# axiom_beta_plugin_module_TE0714_SATA_v0_.net
KiCad netlist of a schematic drawn in EAGLE
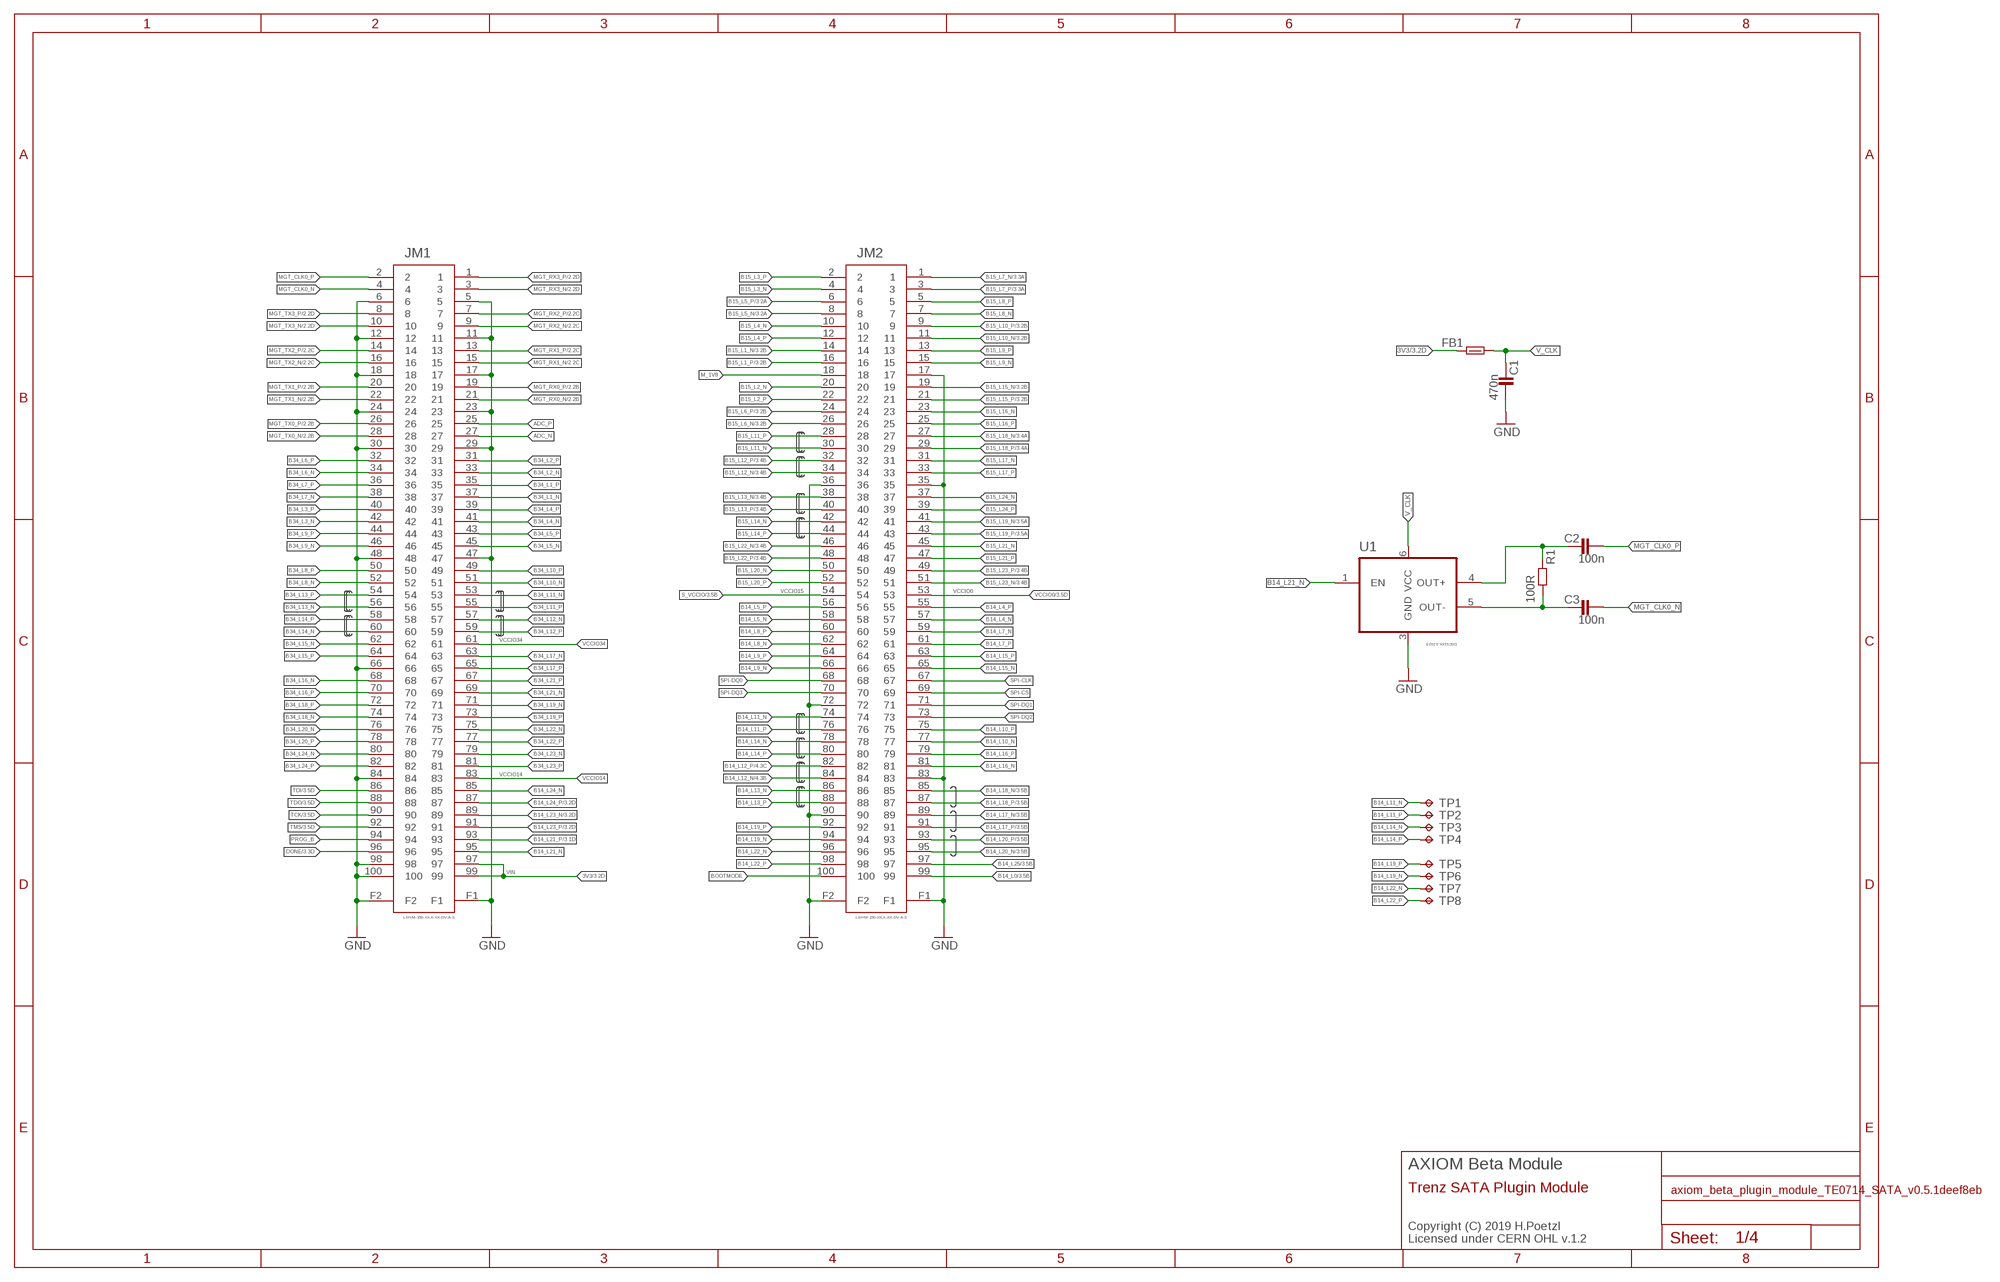
[diagram p0: schematic, sheet 1]
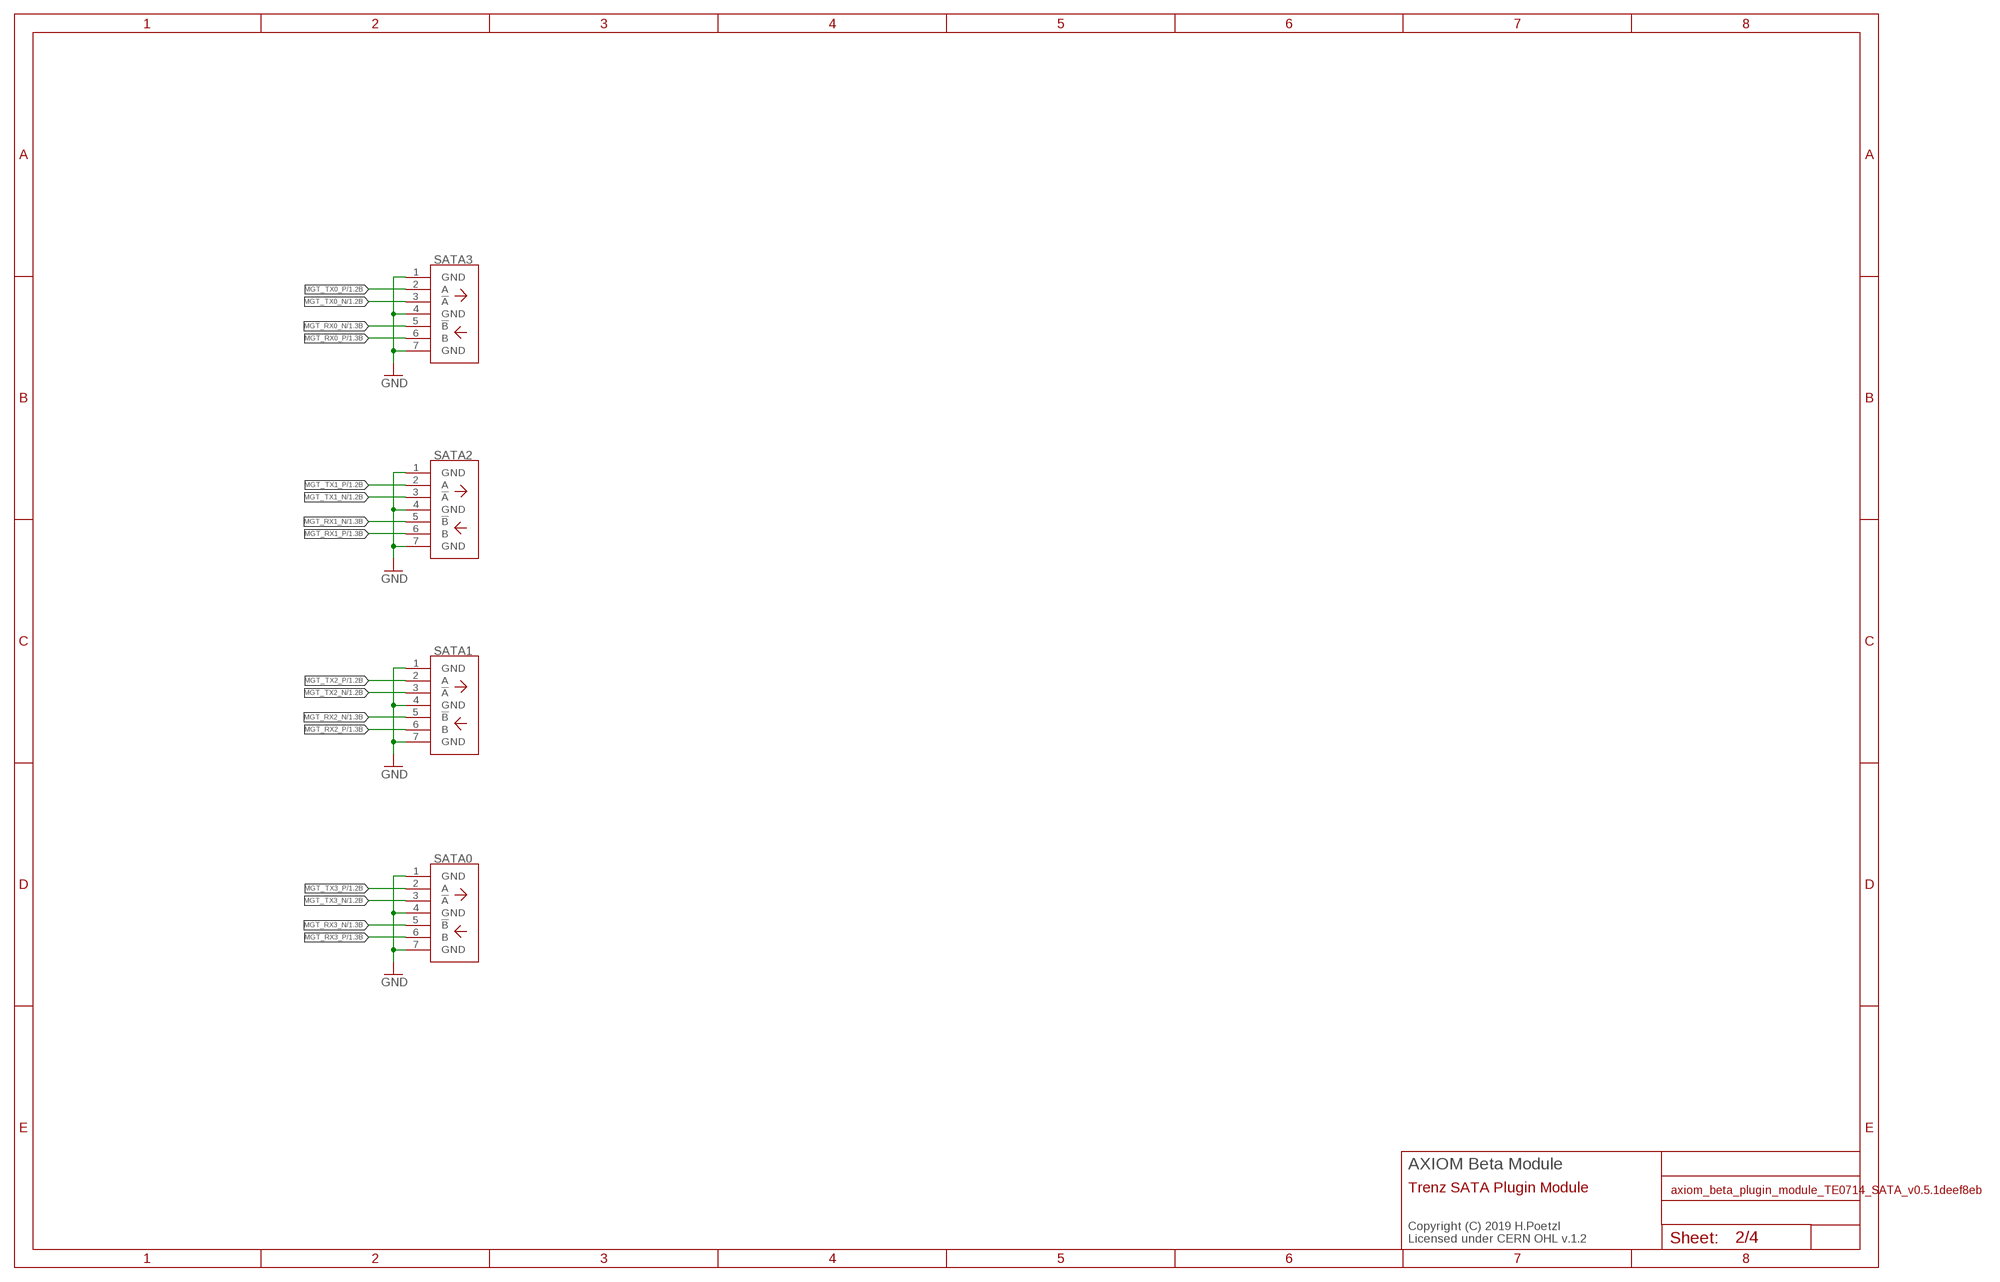
[diagram p1: schematic, sheet 2]
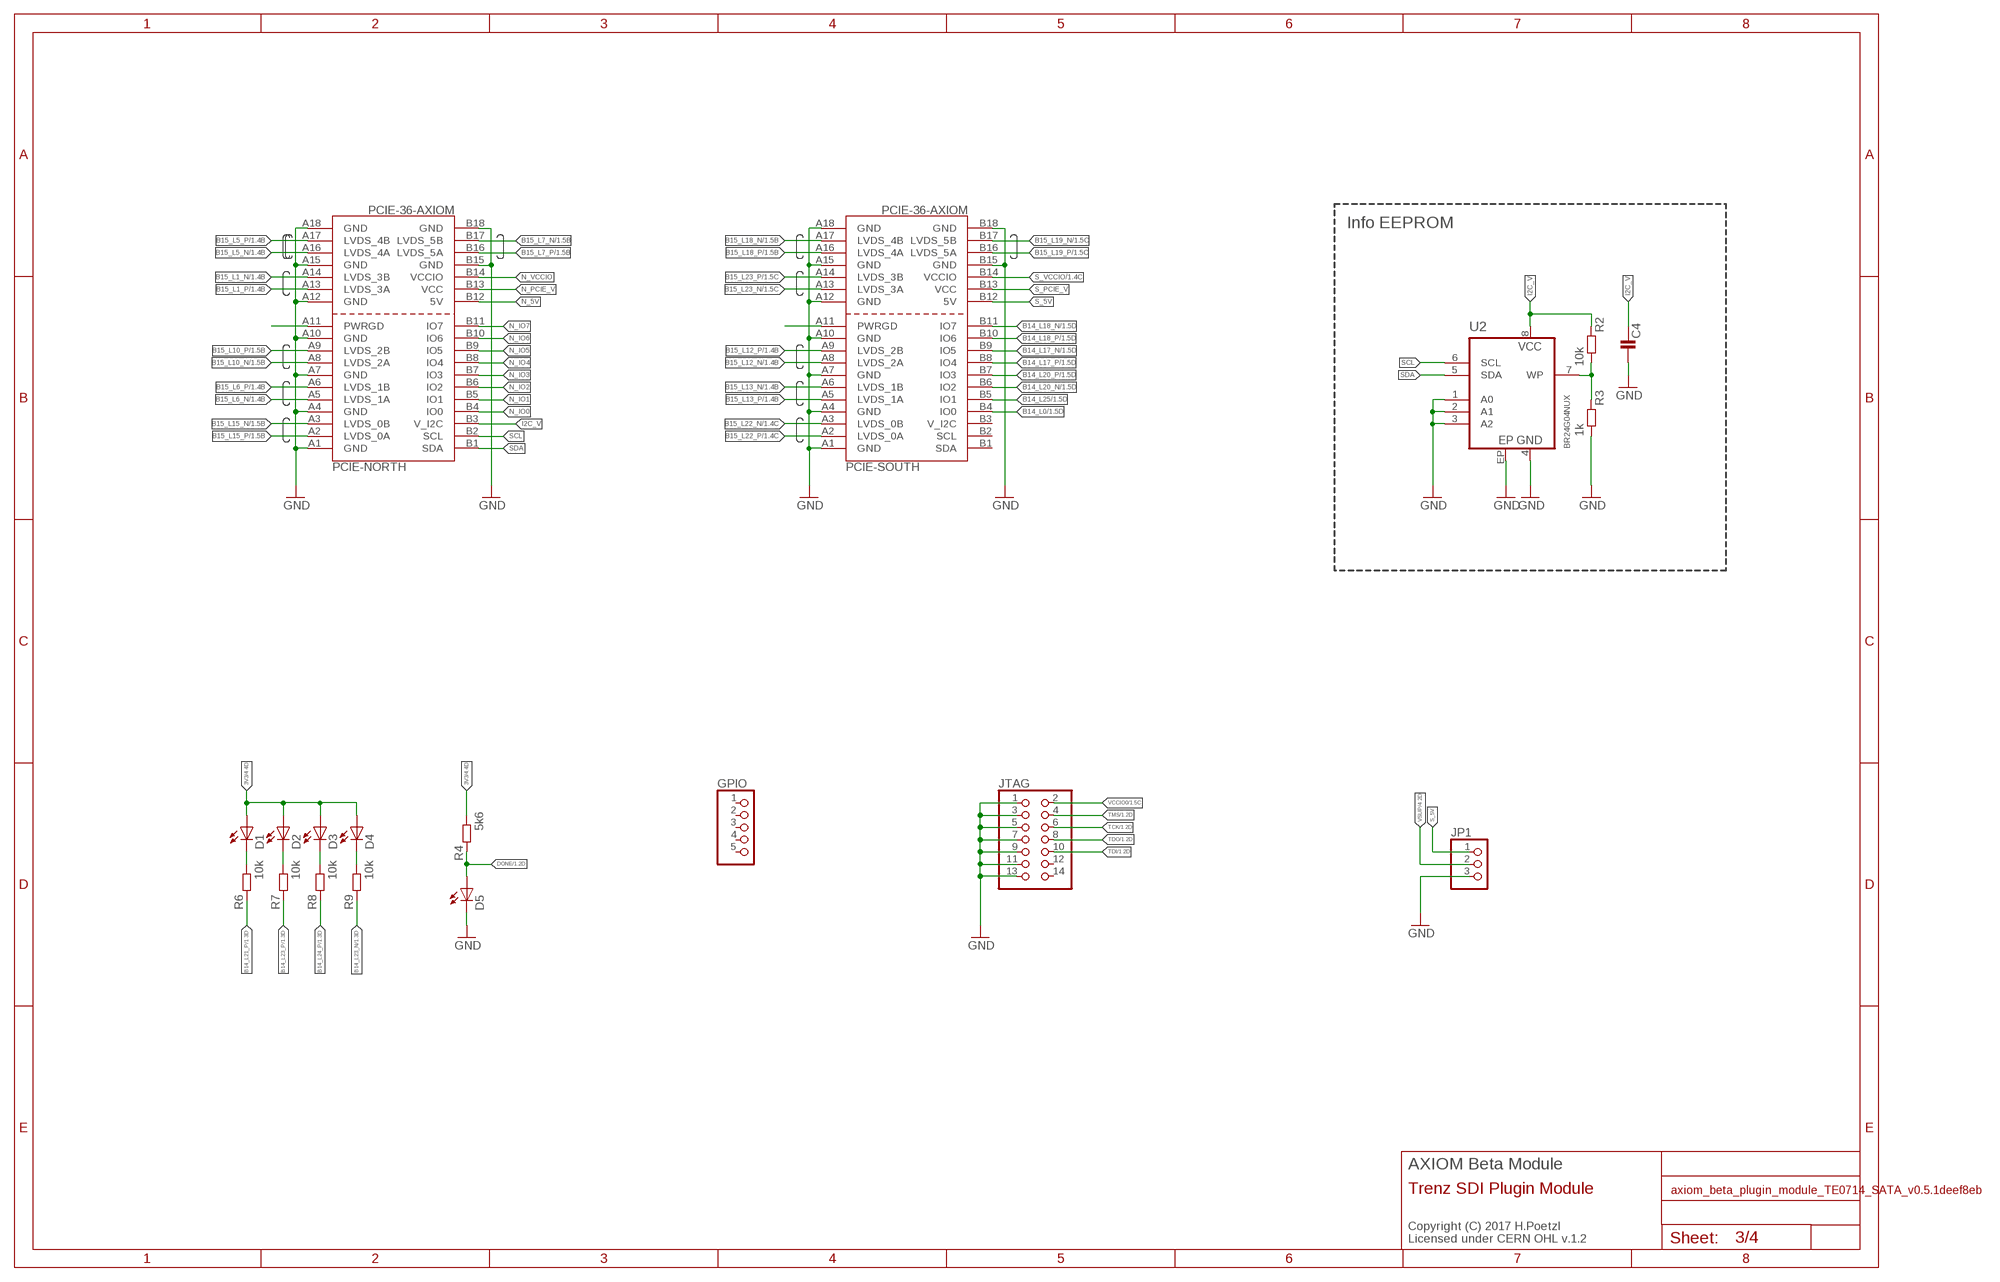
[diagram p2: schematic, sheet 3]
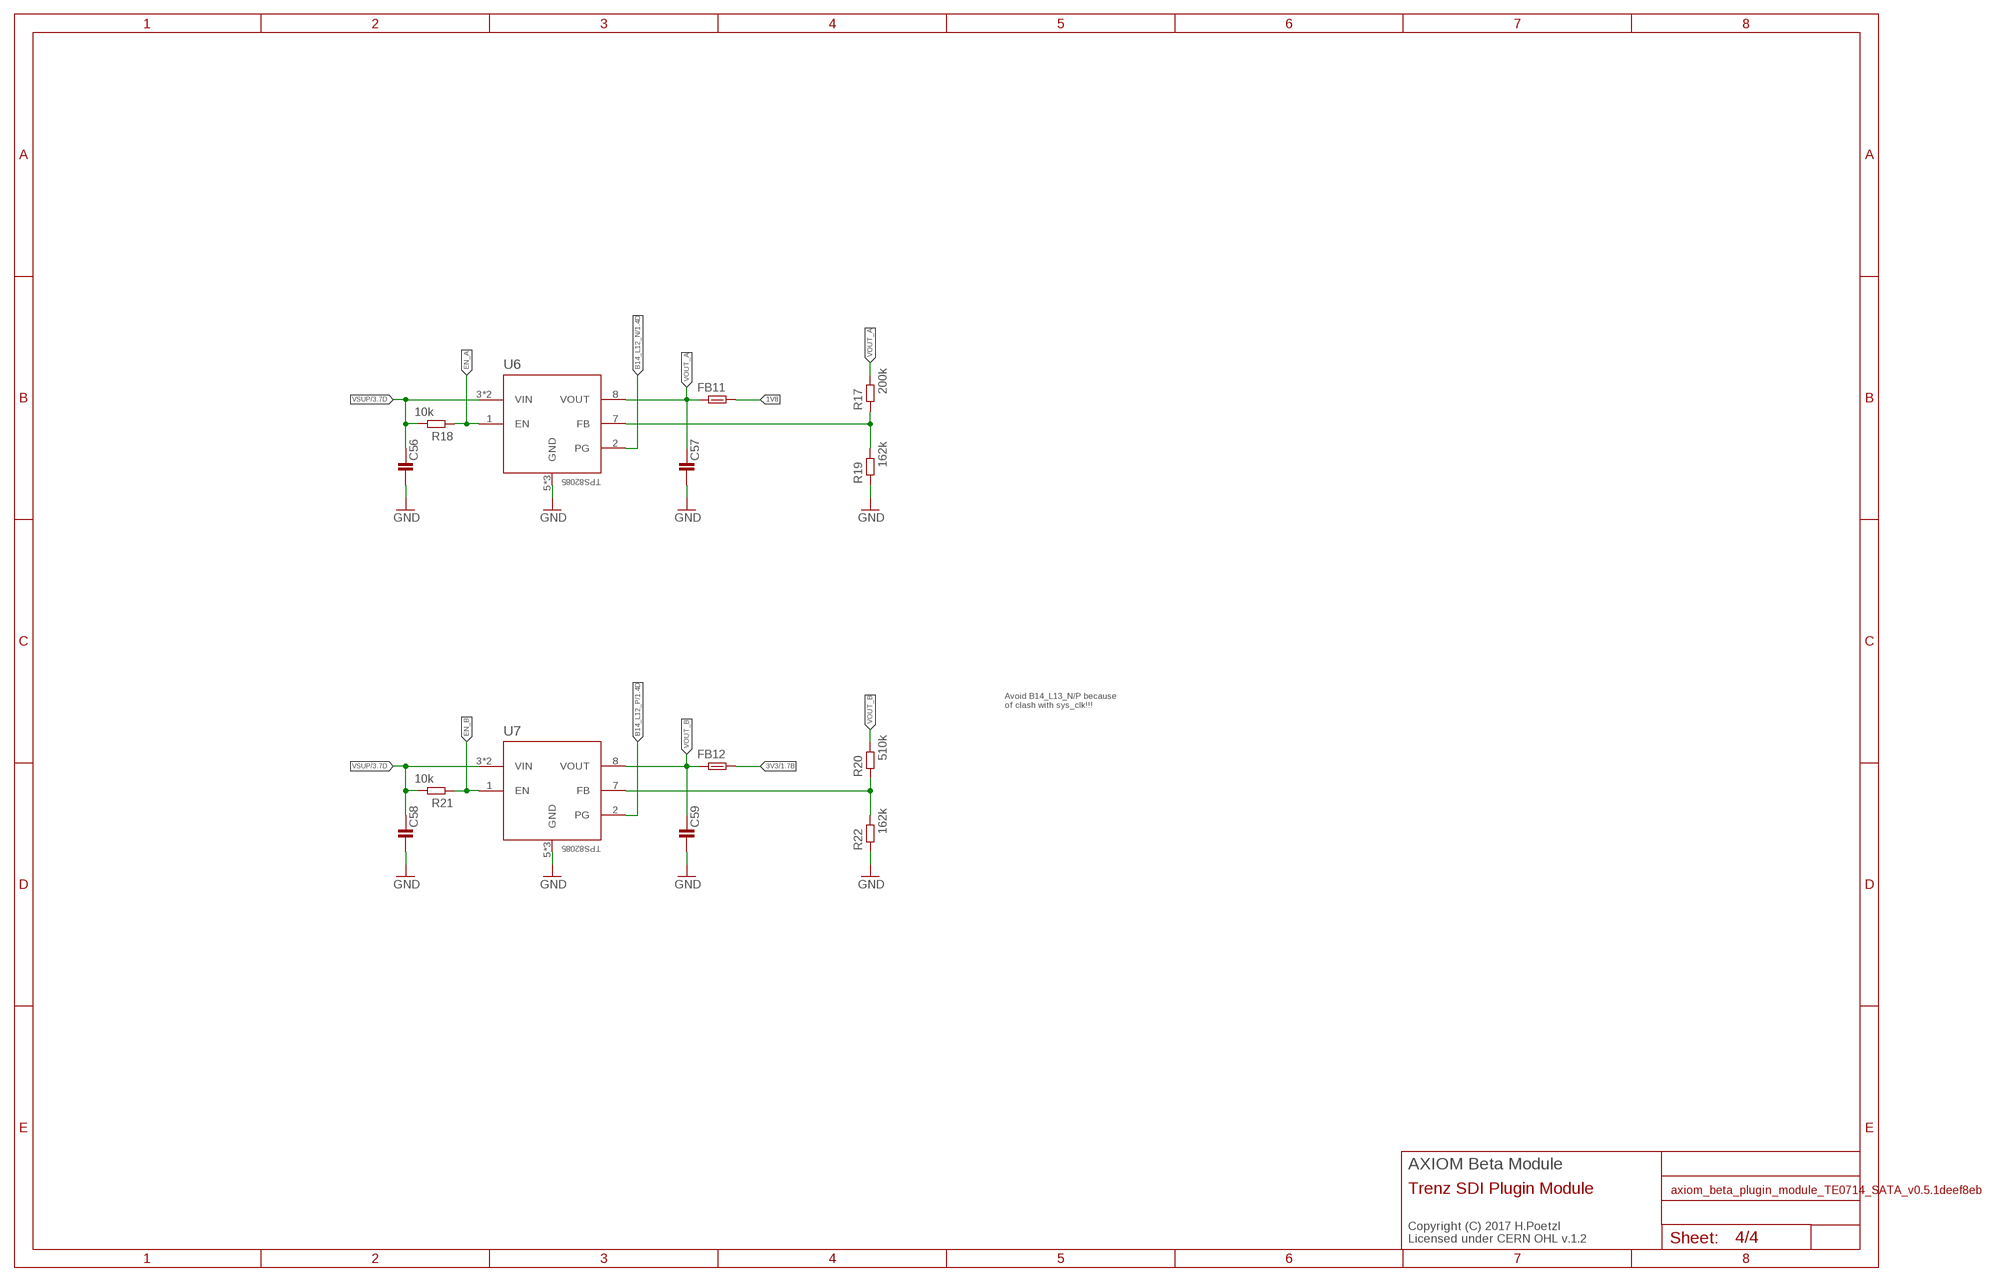
[diagram p3: schematic, sheet 4]

(export (version "E")
  (design (tool "Eeschema 10.0.6"))
  (components
    (comp (ref "C4")
      (value "C0402-B")
      (footprint "eagle-import:0402-B")
      (libsource (lib "eagle-import") (part "C0402-B"))
    )
    (comp (ref "D1")
      (value "LED")
      (footprint "eagle-import:CHIPLED_0603")
      (libsource (lib "eagle-import") (part "LED"))
    )
    (comp (ref "D2")
      (value "LED")
      (footprint "eagle-import:CHIPLED_0603")
      (libsource (lib "eagle-import") (part "LED"))
    )
    (comp (ref "D3")
      (value "LED")
      (footprint "eagle-import:CHIPLED_0603")
      (libsource (lib "eagle-import") (part "LED"))
    )
    (comp (ref "D4")
      (value "LED")
      (footprint "eagle-import:CHIPLED_0603")
      (libsource (lib "eagle-import") (part "LED"))
    )
    (comp (ref "D5")
      (value "LED")
      (footprint "eagle-import:CHIPLED_0603")
      (libsource (lib "eagle-import") (part "LED"))
    )
    (comp (ref "GPIO")
      (value "PINHD-1X05_2.00")
      (footprint "eagle-import:1X05M")
      (libsource (lib "eagle-import") (part "PINHD-1X05_2.00"))
    )
    (comp (ref "JP1")
      (value "PINHD-1X03_2.54-90°-S")
      (footprint "eagle-import:1X03_90-S")
      (libsource (lib "eagle-import") (part "PINHD-1X03_2.54-90°-S"))
    )
    (comp (ref "JTAG")
      (value "PINHD-2X07_2.00")
      (footprint "eagle-import:2X07M")
      (libsource (lib "eagle-import") (part "PINHD-2X07_2.00"))
    )
    (comp (ref "PCIE-NORTH")
      (value "PCIE-36-AXIOM")
      (footprint "eagle-import:PCIE-36-AXIOM")
      (libsource (lib "eagle-import") (part "PCIE-36-AXIOM"))
    )
    (comp (ref "PCIE-SOUTH")
      (value "PCIE-36-AXIOM")
      (footprint "eagle-import:PCIE-36-AXIOM")
      (libsource (lib "eagle-import") (part "PCIE-36-AXIOM"))
    )
    (comp (ref "R2")
      (value "10k")
      (footprint "eagle-import:0402-B")
      (libsource (lib "eagle-import") (part "R0402-B"))
    )
    (comp (ref "R3")
      (value "1k")
      (footprint "eagle-import:0402-B")
      (libsource (lib "eagle-import") (part "R0402-B"))
    )
    (comp (ref "R4")
      (value "5k6")
      (footprint "eagle-import:0402-C")
      (libsource (lib "eagle-import") (part "R0402-C"))
    )
    (comp (ref "R6")
      (value "10k")
      (footprint "eagle-import:0402-C")
      (libsource (lib "eagle-import") (part "R0402-C"))
    )
    (comp (ref "R7")
      (value "10k")
      (footprint "eagle-import:0402-C")
      (libsource (lib "eagle-import") (part "R0402-C"))
    )
    (comp (ref "R8")
      (value "10k")
      (footprint "eagle-import:0402-C")
      (libsource (lib "eagle-import") (part "R0402-C"))
    )
    (comp (ref "R9")
      (value "10k")
      (footprint "eagle-import:0402-C")
      (libsource (lib "eagle-import") (part "R0402-C"))
    )
    (comp (ref "U2")
      (value "BR24G04NUX")
      (footprint "eagle-import:DFN200X300X100-9N")
      (libsource (lib "eagle-import") (part "BR24G04NUX"))
    )
    (comp (ref "SATA0")
      (value "SATA7-VERT")
      (footprint "eagle-import:SATA7-VERT")
      (libsource (lib "eagle-import") (part "SATA7-VERT"))
    )
    (comp (ref "SATA1")
      (value "SATA7-VERT")
      (footprint "eagle-import:SATA7-VERT")
      (libsource (lib "eagle-import") (part "SATA7-VERT"))
    )
    (comp (ref "SATA2")
      (value "SATA7-VERT")
      (footprint "eagle-import:SATA7-VERT")
      (libsource (lib "eagle-import") (part "SATA7-VERT"))
    )
    (comp (ref "SATA3")
      (value "SATA7-VERT")
      (footprint "eagle-import:SATA7-VERT")
      (libsource (lib "eagle-import") (part "SATA7-VERT"))
    )
    (comp (ref "C56")
      (value "C0603-C")
      (footprint "eagle-import:0603-C")
      (libsource (lib "eagle-import") (part "C0603-C"))
    )
    (comp (ref "C57")
      (value "C0603-C")
      (footprint "eagle-import:0603-C")
      (libsource (lib "eagle-import") (part "C0603-C"))
    )
    (comp (ref "C58")
      (value "C0603-C")
      (footprint "eagle-import:0603-C")
      (libsource (lib "eagle-import") (part "C0603-C"))
    )
    (comp (ref "C59")
      (value "C0603-C")
      (footprint "eagle-import:0603-C")
      (libsource (lib "eagle-import") (part "C0603-C"))
    )
    (comp (ref "FB11")
      (value "FB0603-C")
      (footprint "eagle-import:0603-C")
      (libsource (lib "eagle-import") (part "FB0603-C"))
    )
    (comp (ref "FB12")
      (value "FB0603-C")
      (footprint "eagle-import:0603-C")
      (libsource (lib "eagle-import") (part "FB0603-C"))
    )
    (comp (ref "R17")
      (value "200k")
      (footprint "eagle-import:0201-C")
      (libsource (lib "eagle-import") (part "R0201-C"))
    )
    (comp (ref "R18")
      (value "10k")
      (footprint "eagle-import:0201-C")
      (libsource (lib "eagle-import") (part "R0201-C"))
    )
    (comp (ref "R19")
      (value "162k")
      (footprint "eagle-import:0201-C")
      (libsource (lib "eagle-import") (part "R0201-C"))
    )
    (comp (ref "R20")
      (value "510k")
      (footprint "eagle-import:0201-C")
      (libsource (lib "eagle-import") (part "R0201-C"))
    )
    (comp (ref "R21")
      (value "10k")
      (footprint "eagle-import:0201-C")
      (libsource (lib "eagle-import") (part "R0201-C"))
    )
    (comp (ref "R22")
      (value "162k")
      (footprint "eagle-import:0201-C")
      (libsource (lib "eagle-import") (part "R0201-C"))
    )
    (comp (ref "U6")
      (value "TPS82085")
      (footprint "eagle-import:MICROSIP")
      (libsource (lib "eagle-import") (part "TPS82085"))
    )
    (comp (ref "U7")
      (value "TPS82085")
      (footprint "eagle-import:MICROSIP")
      (libsource (lib "eagle-import") (part "TPS82085"))
    )
    (comp (ref "C1")
      (value "470n")
      (footprint "eagle-import:0402-C")
      (libsource (lib "eagle-import") (part "C0402-C"))
    )
    (comp (ref "C2")
      (value "100n")
      (footprint "eagle-import:0201-C")
      (libsource (lib "eagle-import") (part "C0201-C"))
    )
    (comp (ref "C3")
      (value "100n")
      (footprint "eagle-import:0201-C")
      (libsource (lib "eagle-import") (part "C0201-C"))
    )
    (comp (ref "FB1")
      (value "FB0402-C")
      (footprint "eagle-import:0402-C")
      (libsource (lib "eagle-import") (part "FB0402-C"))
    )
    (comp (ref "JM1")
      (value "LSHM-150-XX.X-XX-DV-A-S")
      (footprint "eagle-import:LSHM-150-XX.X-XX-DV-A-S")
      (libsource (lib "eagle-import") (part "LSHM-150-XX.X-XX-DV-A-S"))
    )
    (comp (ref "JM2")
      (value "LSHM-150-XX.X-XX-DV-A-S")
      (footprint "eagle-import:LSHM-150-XX.X-XX-DV-A-S")
      (libsource (lib "eagle-import") (part "LSHM-150-XX.X-XX-DV-A-S"))
    )
    (comp (ref "R1")
      (value "100R")
      (footprint "eagle-import:0201-C")
      (libsource (lib "eagle-import") (part "R0201-C"))
    )
    (comp (ref "TP1")
      (value "TPTP08R")
      (footprint "eagle-import:TP08R")
      (libsource (lib "eagle-import") (part "TPTP08R"))
    )
    (comp (ref "TP2")
      (value "TPTP08R")
      (footprint "eagle-import:TP08R")
      (libsource (lib "eagle-import") (part "TPTP08R"))
    )
    (comp (ref "TP3")
      (value "TPTP08R")
      (footprint "eagle-import:TP08R")
      (libsource (lib "eagle-import") (part "TPTP08R"))
    )
    (comp (ref "TP4")
      (value "TPTP08R")
      (footprint "eagle-import:TP08R")
      (libsource (lib "eagle-import") (part "TPTP08R"))
    )
    (comp (ref "TP5")
      (value "TPTP10R")
      (footprint "eagle-import:TP10R")
      (libsource (lib "eagle-import") (part "TPTP10R"))
    )
    (comp (ref "TP6")
      (value "TPTP10R")
      (footprint "eagle-import:TP10R")
      (libsource (lib "eagle-import") (part "TPTP10R"))
    )
    (comp (ref "TP7")
      (value "TPTP10R")
      (footprint "eagle-import:TP10R")
      (libsource (lib "eagle-import") (part "TPTP10R"))
    )
    (comp (ref "TP8")
      (value "TPTP10R")
      (footprint "eagle-import:TP10R")
      (libsource (lib "eagle-import") (part "TPTP10R"))
    )
    (comp (ref "U1")
      (value "DSC11XX-3.2X2.5")
      (footprint "eagle-import:3.2X2.5")
      (libsource (lib "eagle-import") (part "DSC11XX-3.2X2.5"))
    )
  )
  (nets
    (net (code "1") (name "1V8") (class "Default")
      (node (ref "FB11") (pin "2") (pinfunction "2_2") (pintype "passive"))
    )
    (net (code "2") (name "3V3") (class "Default")
      (node (ref "D1") (pin "A") (pinfunction "A_A") (pintype "passive"))
      (node (ref "D2") (pin "A") (pinfunction "A_A") (pintype "passive"))
      (node (ref "D3") (pin "A") (pinfunction "A_A") (pintype "passive"))
      (node (ref "D4") (pin "A") (pinfunction "A_A") (pintype "passive"))
      (node (ref "FB1") (pin "1") (pinfunction "1_1") (pintype "passive"))
      (node (ref "FB12") (pin "2") (pinfunction "2_2") (pintype "passive"))
      (node (ref "JM1") (pin "97") (pinfunction "97_97") (pintype "bidirectional"))
      (node (ref "JM1") (pin "99") (pinfunction "99_99") (pintype "bidirectional"))
      (node (ref "R4") (pin "2") (pinfunction "2_2") (pintype "passive"))
    )
    (net (code "3") (name "ADC_N") (class "Default")
      (node (ref "JM1") (pin "27") (pinfunction "27_27") (pintype "bidirectional"))
    )
    (net (code "4") (name "ADC_P") (class "Default")
      (node (ref "JM1") (pin "25") (pinfunction "25_25") (pintype "bidirectional"))
    )
    (net (code "5") (name "B14_L0") (class "Default")
      (node (ref "JM2") (pin "99") (pinfunction "99_99") (pintype "bidirectional"))
      (node (ref "PCIE-SOUTH") (pin "B4") (pinfunction "IO0_B4") (pintype "passive"))
    )
    (net (code "6") (name "B14_L4_N") (class "Default")
      (node (ref "JM2") (pin "57") (pinfunction "57_57") (pintype "bidirectional"))
    )
    (net (code "7") (name "B14_L4_P") (class "Default")
      (node (ref "JM2") (pin "55") (pinfunction "55_55") (pintype "bidirectional"))
    )
    (net (code "8") (name "B14_L5_N") (class "Default")
      (node (ref "JM2") (pin "58") (pinfunction "58_58") (pintype "bidirectional"))
    )
    (net (code "9") (name "B14_L5_P") (class "Default")
      (node (ref "JM2") (pin "56") (pinfunction "56_56") (pintype "bidirectional"))
    )
    (net (code "10") (name "B14_L7_N") (class "Default")
      (node (ref "JM2") (pin "59") (pinfunction "59_59") (pintype "bidirectional"))
    )
    (net (code "11") (name "B14_L7_P") (class "Default")
      (node (ref "JM2") (pin "61") (pinfunction "61_61") (pintype "bidirectional"))
    )
    (net (code "12") (name "B14_L8_N") (class "Default")
      (node (ref "JM2") (pin "62") (pinfunction "62_62") (pintype "bidirectional"))
    )
    (net (code "13") (name "B14_L8_P") (class "Default")
      (node (ref "JM2") (pin "60") (pinfunction "60_60") (pintype "bidirectional"))
    )
    (net (code "14") (name "B14_L9_N") (class "Default")
      (node (ref "JM2") (pin "66") (pinfunction "66_66") (pintype "bidirectional"))
    )
    (net (code "15") (name "B14_L9_P") (class "Default")
      (node (ref "JM2") (pin "64") (pinfunction "64_64") (pintype "bidirectional"))
    )
    (net (code "16") (name "B14_L10_N") (class "Default")
      (node (ref "JM2") (pin "77") (pinfunction "77_77") (pintype "bidirectional"))
    )
    (net (code "17") (name "B14_L10_P") (class "Default")
      (node (ref "JM2") (pin "75") (pinfunction "75_75") (pintype "bidirectional"))
    )
    (net (code "18") (name "B14_L11_N") (class "Default")
      (node (ref "JM2") (pin "74") (pinfunction "74_74") (pintype "bidirectional"))
      (node (ref "TP1") (pin "TP") (pinfunction "TP_TP") (pintype "input"))
    )
    (net (code "19") (name "B14_L11_P") (class "Default")
      (node (ref "JM2") (pin "76") (pinfunction "76_76") (pintype "bidirectional"))
      (node (ref "TP2") (pin "TP") (pinfunction "TP_TP") (pintype "input"))
    )
    (net (code "20") (name "B14_L12_N") (class "Default")
      (node (ref "JM2") (pin "84") (pinfunction "84_84") (pintype "bidirectional"))
      (node (ref "U6") (pin "2") (pinfunction "PG_2") (pintype "power_in"))
    )
    (net (code "21") (name "B14_L12_P") (class "Default")
      (node (ref "JM2") (pin "82") (pinfunction "82_82") (pintype "bidirectional"))
      (node (ref "U7") (pin "2") (pinfunction "PG_2") (pintype "power_in"))
    )
    (net (code "22") (name "B14_L13_N") (class "Default")
      (node (ref "JM2") (pin "86") (pinfunction "86_86") (pintype "bidirectional"))
    )
    (net (code "23") (name "B14_L13_P") (class "Default")
      (node (ref "JM2") (pin "88") (pinfunction "88_88") (pintype "bidirectional"))
    )
    (net (code "24") (name "B14_L14_N") (class "Default")
      (node (ref "JM2") (pin "78") (pinfunction "78_78") (pintype "bidirectional"))
      (node (ref "TP3") (pin "TP") (pinfunction "TP_TP") (pintype "input"))
    )
    (net (code "25") (name "B14_L14_P") (class "Default")
      (node (ref "JM2") (pin "80") (pinfunction "80_80") (pintype "bidirectional"))
      (node (ref "TP4") (pin "TP") (pinfunction "TP_TP") (pintype "input"))
    )
    (net (code "26") (name "B14_L15_N") (class "Default")
      (node (ref "JM2") (pin "65") (pinfunction "65_65") (pintype "bidirectional"))
    )
    (net (code "27") (name "B14_L15_P") (class "Default")
      (node (ref "JM2") (pin "63") (pinfunction "63_63") (pintype "bidirectional"))
    )
    (net (code "28") (name "B14_L16_N") (class "Default")
      (node (ref "JM2") (pin "81") (pinfunction "81_81") (pintype "bidirectional"))
    )
    (net (code "29") (name "B14_L16_P") (class "Default")
      (node (ref "JM2") (pin "79") (pinfunction "79_79") (pintype "bidirectional"))
    )
    (net (code "30") (name "B14_L17_N") (class "Default")
      (node (ref "JM2") (pin "89") (pinfunction "89_89") (pintype "bidirectional"))
      (node (ref "PCIE-SOUTH") (pin "B9") (pinfunction "IO5_B9") (pintype "passive"))
    )
    (net (code "31") (name "B14_L17_P") (class "Default")
      (node (ref "JM2") (pin "91") (pinfunction "91_91") (pintype "bidirectional"))
      (node (ref "PCIE-SOUTH") (pin "B8") (pinfunction "IO4_B8") (pintype "passive"))
    )
    (net (code "32") (name "B14_L18_N") (class "Default")
      (node (ref "JM2") (pin "85") (pinfunction "85_85") (pintype "bidirectional"))
      (node (ref "PCIE-SOUTH") (pin "B11") (pinfunction "IO7_B11") (pintype "passive"))
    )
    (net (code "33") (name "B14_L18_P") (class "Default")
      (node (ref "JM2") (pin "87") (pinfunction "87_87") (pintype "bidirectional"))
      (node (ref "PCIE-SOUTH") (pin "B10") (pinfunction "IO6_B10") (pintype "passive"))
    )
    (net (code "34") (name "B14_L19_N") (class "Default")
      (node (ref "JM2") (pin "94") (pinfunction "94_94") (pintype "bidirectional"))
      (node (ref "TP6") (pin "TP") (pinfunction "TP_TP") (pintype "input"))
    )
    (net (code "35") (name "B14_L19_P") (class "Default")
      (node (ref "JM2") (pin "92") (pinfunction "92_92") (pintype "bidirectional"))
      (node (ref "TP5") (pin "TP") (pinfunction "TP_TP") (pintype "input"))
    )
    (net (code "36") (name "B14_L20_N") (class "Default")
      (node (ref "JM2") (pin "95") (pinfunction "95_95") (pintype "bidirectional"))
      (node (ref "PCIE-SOUTH") (pin "B6") (pinfunction "IO2_B6") (pintype "passive"))
    )
    (net (code "37") (name "B14_L20_P") (class "Default")
      (node (ref "JM2") (pin "93") (pinfunction "93_93") (pintype "bidirectional"))
      (node (ref "PCIE-SOUTH") (pin "B7") (pinfunction "IO3_B7") (pintype "passive"))
    )
    (net (code "38") (name "B14_L21_N") (class "Default")
      (node (ref "JM1") (pin "95") (pinfunction "95_95") (pintype "bidirectional"))
      (node (ref "U1") (pin "1") (pinfunction "EN_1") (pintype "input"))
    )
    (net (code "39") (name "B14_L21_P") (class "Default")
      (node (ref "JM1") (pin "93") (pinfunction "93_93") (pintype "bidirectional"))
      (node (ref "R6") (pin "1") (pinfunction "1_1") (pintype "passive"))
    )
    (net (code "40") (name "B14_L22_N") (class "Default")
      (node (ref "JM2") (pin "96") (pinfunction "96_96") (pintype "bidirectional"))
      (node (ref "TP7") (pin "TP") (pinfunction "TP_TP") (pintype "input"))
    )
    (net (code "41") (name "B14_L22_P") (class "Default")
      (node (ref "JM2") (pin "98") (pinfunction "98_98") (pintype "bidirectional"))
      (node (ref "TP8") (pin "TP") (pinfunction "TP_TP") (pintype "input"))
    )
    (net (code "42") (name "B14_L23_N") (class "Default")
      (node (ref "JM1") (pin "89") (pinfunction "89_89") (pintype "bidirectional"))
      (node (ref "R9") (pin "1") (pinfunction "1_1") (pintype "passive"))
    )
    (net (code "43") (name "B14_L23_P") (class "Default")
      (node (ref "JM1") (pin "91") (pinfunction "91_91") (pintype "bidirectional"))
      (node (ref "R7") (pin "1") (pinfunction "1_1") (pintype "passive"))
    )
    (net (code "44") (name "B14_L24_N") (class "Default")
      (node (ref "JM1") (pin "85") (pinfunction "85_85") (pintype "bidirectional"))
    )
    (net (code "45") (name "B14_L24_P") (class "Default")
      (node (ref "JM1") (pin "87") (pinfunction "87_87") (pintype "bidirectional"))
      (node (ref "R8") (pin "1") (pinfunction "1_1") (pintype "passive"))
    )
    (net (code "46") (name "B14_L25") (class "Default")
      (node (ref "JM2") (pin "97") (pinfunction "97_97") (pintype "bidirectional"))
      (node (ref "PCIE-SOUTH") (pin "B5") (pinfunction "IO1_B5") (pintype "passive"))
    )
    (net (code "47") (name "B15_L1_N") (class "Default")
      (node (ref "JM2") (pin "14") (pinfunction "14_14") (pintype "bidirectional"))
      (node (ref "PCIE-NORTH") (pin "A14") (pinfunction "LVDS_3B_A14") (pintype "passive"))
    )
    (net (code "48") (name "B15_L1_P") (class "Default")
      (node (ref "JM2") (pin "16") (pinfunction "16_16") (pintype "bidirectional"))
      (node (ref "PCIE-NORTH") (pin "A13") (pinfunction "LVDS_3A_A13") (pintype "passive"))
    )
    (net (code "49") (name "B15_L2_N") (class "Default")
      (node (ref "JM2") (pin "20") (pinfunction "20_20") (pintype "bidirectional"))
    )
    (net (code "50") (name "B15_L2_P") (class "Default")
      (node (ref "JM2") (pin "22") (pinfunction "22_22") (pintype "bidirectional"))
    )
    (net (code "51") (name "B15_L3_N") (class "Default")
      (node (ref "JM2") (pin "4") (pinfunction "4_4") (pintype "bidirectional"))
    )
    (net (code "52") (name "B15_L3_P") (class "Default")
      (node (ref "JM2") (pin "2") (pinfunction "2_2") (pintype "bidirectional"))
    )
    (net (code "53") (name "B15_L4_N") (class "Default")
      (node (ref "JM2") (pin "10") (pinfunction "10_10") (pintype "bidirectional"))
    )
    (net (code "54") (name "B15_L4_P") (class "Default")
      (node (ref "JM2") (pin "12") (pinfunction "12_12") (pintype "bidirectional"))
    )
    (net (code "55") (name "B15_L5_N") (class "Default")
      (node (ref "JM2") (pin "8") (pinfunction "8_8") (pintype "bidirectional"))
      (node (ref "PCIE-NORTH") (pin "A16") (pinfunction "LVDS_4A_A16") (pintype "passive"))
    )
    (net (code "56") (name "B15_L5_P") (class "Default")
      (node (ref "JM2") (pin "6") (pinfunction "6_6") (pintype "bidirectional"))
      (node (ref "PCIE-NORTH") (pin "A17") (pinfunction "LVDS_4B_A17") (pintype "passive"))
    )
    (net (code "57") (name "B15_L6_N") (class "Default")
      (node (ref "JM2") (pin "26") (pinfunction "26_26") (pintype "bidirectional"))
      (node (ref "PCIE-NORTH") (pin "A5") (pinfunction "LVDS_1A_A5") (pintype "passive"))
    )
    (net (code "58") (name "B15_L6_P") (class "Default")
      (node (ref "JM2") (pin "24") (pinfunction "24_24") (pintype "bidirectional"))
      (node (ref "PCIE-NORTH") (pin "A6") (pinfunction "LVDS_1B_A6") (pintype "passive"))
    )
    (net (code "59") (name "B15_L7_N") (class "Default")
      (node (ref "JM2") (pin "1") (pinfunction "1_1") (pintype "bidirectional"))
      (node (ref "PCIE-NORTH") (pin "B17") (pinfunction "LVDS_5B_B17") (pintype "passive"))
    )
    (net (code "60") (name "B15_L7_P") (class "Default")
      (node (ref "JM2") (pin "3") (pinfunction "3_3") (pintype "bidirectional"))
      (node (ref "PCIE-NORTH") (pin "B16") (pinfunction "LVDS_5A_B16") (pintype "passive"))
    )
    (net (code "61") (name "B15_L8_N") (class "Default")
      (node (ref "JM2") (pin "7") (pinfunction "7_7") (pintype "bidirectional"))
    )
    (net (code "62") (name "B15_L8_P") (class "Default")
      (node (ref "JM2") (pin "5") (pinfunction "5_5") (pintype "bidirectional"))
    )
    (net (code "63") (name "B15_L9_N") (class "Default")
      (node (ref "JM2") (pin "15") (pinfunction "15_15") (pintype "bidirectional"))
    )
    (net (code "64") (name "B15_L9_P") (class "Default")
      (node (ref "JM2") (pin "13") (pinfunction "13_13") (pintype "bidirectional"))
    )
    (net (code "65") (name "B15_L10_N") (class "Default")
      (node (ref "JM2") (pin "11") (pinfunction "11_11") (pintype "bidirectional"))
      (node (ref "PCIE-NORTH") (pin "A8") (pinfunction "LVDS_2A_A8") (pintype "passive"))
    )
    (net (code "66") (name "B15_L10_P") (class "Default")
      (node (ref "JM2") (pin "9") (pinfunction "9_9") (pintype "bidirectional"))
      (node (ref "PCIE-NORTH") (pin "A9") (pinfunction "LVDS_2B_A9") (pintype "passive"))
    )
    (net (code "67") (name "B15_L11_N") (class "Default")
      (node (ref "JM2") (pin "30") (pinfunction "30_30") (pintype "bidirectional"))
    )
    (net (code "68") (name "B15_L11_P") (class "Default")
      (node (ref "JM2") (pin "28") (pinfunction "28_28") (pintype "bidirectional"))
    )
    (net (code "69") (name "B15_L12_N") (class "Default")
      (node (ref "JM2") (pin "34") (pinfunction "34_34") (pintype "bidirectional"))
      (node (ref "PCIE-SOUTH") (pin "A8") (pinfunction "LVDS_2A_A8") (pintype "passive"))
    )
    (net (code "70") (name "B15_L12_P") (class "Default")
      (node (ref "JM2") (pin "32") (pinfunction "32_32") (pintype "bidirectional"))
      (node (ref "PCIE-SOUTH") (pin "A9") (pinfunction "LVDS_2B_A9") (pintype "passive"))
    )
    (net (code "71") (name "B15_L13_N") (class "Default")
      (node (ref "JM2") (pin "38") (pinfunction "38_38") (pintype "bidirectional"))
      (node (ref "PCIE-SOUTH") (pin "A6") (pinfunction "LVDS_1B_A6") (pintype "passive"))
    )
    (net (code "72") (name "B15_L13_P") (class "Default")
      (node (ref "JM2") (pin "40") (pinfunction "40_40") (pintype "bidirectional"))
      (node (ref "PCIE-SOUTH") (pin "A5") (pinfunction "LVDS_1A_A5") (pintype "passive"))
    )
    (net (code "73") (name "B15_L14_N") (class "Default")
      (node (ref "JM2") (pin "42") (pinfunction "42_42") (pintype "bidirectional"))
    )
    (net (code "74") (name "B15_L14_P") (class "Default")
      (node (ref "JM2") (pin "44") (pinfunction "44_44") (pintype "bidirectional"))
    )
    (net (code "75") (name "B15_L15_N") (class "Default")
      (node (ref "JM2") (pin "19") (pinfunction "19_19") (pintype "bidirectional"))
      (node (ref "PCIE-NORTH") (pin "A3") (pinfunction "LVDS_0B_A3") (pintype "passive"))
    )
    (net (code "76") (name "B15_L15_P") (class "Default")
      (node (ref "JM2") (pin "21") (pinfunction "21_21") (pintype "bidirectional"))
      (node (ref "PCIE-NORTH") (pin "A2") (pinfunction "LVDS_0A_A2") (pintype "passive"))
    )
    (net (code "77") (name "B15_L16_N") (class "Default")
      (node (ref "JM2") (pin "23") (pinfunction "23_23") (pintype "bidirectional"))
    )
    (net (code "78") (name "B15_L16_P") (class "Default")
      (node (ref "JM2") (pin "25") (pinfunction "25_25") (pintype "bidirectional"))
    )
    (net (code "79") (name "B15_L17_N") (class "Default")
      (node (ref "JM2") (pin "31") (pinfunction "31_31") (pintype "bidirectional"))
    )
    (net (code "80") (name "B15_L17_P") (class "Default")
      (node (ref "JM2") (pin "33") (pinfunction "33_33") (pintype "bidirectional"))
    )
    (net (code "81") (name "B15_L18_N") (class "Default")
      (node (ref "JM2") (pin "27") (pinfunction "27_27") (pintype "bidirectional"))
      (node (ref "PCIE-SOUTH") (pin "A17") (pinfunction "LVDS_4B_A17") (pintype "passive"))
    )
    (net (code "82") (name "B15_L18_P") (class "Default")
      (node (ref "JM2") (pin "29") (pinfunction "29_29") (pintype "bidirectional"))
      (node (ref "PCIE-SOUTH") (pin "A16") (pinfunction "LVDS_4A_A16") (pintype "passive"))
    )
    (net (code "83") (name "B15_L19_N") (class "Default")
      (node (ref "JM2") (pin "41") (pinfunction "41_41") (pintype "bidirectional"))
      (node (ref "PCIE-SOUTH") (pin "B17") (pinfunction "LVDS_5B_B17") (pintype "passive"))
    )
    (net (code "84") (name "B15_L19_P") (class "Default")
      (node (ref "JM2") (pin "43") (pinfunction "43_43") (pintype "bidirectional"))
      (node (ref "PCIE-SOUTH") (pin "B16") (pinfunction "LVDS_5A_B16") (pintype "passive"))
    )
    (net (code "85") (name "B15_L20_N") (class "Default")
      (node (ref "JM2") (pin "50") (pinfunction "50_50") (pintype "bidirectional"))
    )
    (net (code "86") (name "B15_L20_P") (class "Default")
      (node (ref "JM2") (pin "52") (pinfunction "52_52") (pintype "bidirectional"))
    )
    (net (code "87") (name "B15_L21_N") (class "Default")
      (node (ref "JM2") (pin "45") (pinfunction "45_45") (pintype "bidirectional"))
    )
    (net (code "88") (name "B15_L21_P") (class "Default")
      (node (ref "JM2") (pin "47") (pinfunction "47_47") (pintype "bidirectional"))
    )
    (net (code "89") (name "B15_L22_N") (class "Default")
      (node (ref "JM2") (pin "46") (pinfunction "46_46") (pintype "bidirectional"))
      (node (ref "PCIE-SOUTH") (pin "A3") (pinfunction "LVDS_0B_A3") (pintype "passive"))
    )
    (net (code "90") (name "B15_L22_P") (class "Default")
      (node (ref "JM2") (pin "48") (pinfunction "48_48") (pintype "bidirectional"))
      (node (ref "PCIE-SOUTH") (pin "A2") (pinfunction "LVDS_0A_A2") (pintype "passive"))
    )
    (net (code "91") (name "B15_L23_N") (class "Default")
      (node (ref "JM2") (pin "51") (pinfunction "51_51") (pintype "bidirectional"))
      (node (ref "PCIE-SOUTH") (pin "A13") (pinfunction "LVDS_3A_A13") (pintype "passive"))
    )
    (net (code "92") (name "B15_L23_P") (class "Default")
      (node (ref "JM2") (pin "49") (pinfunction "49_49") (pintype "bidirectional"))
      (node (ref "PCIE-SOUTH") (pin "A14") (pinfunction "LVDS_3B_A14") (pintype "passive"))
    )
    (net (code "93") (name "B15_L24_N") (class "Default")
      (node (ref "JM2") (pin "37") (pinfunction "37_37") (pintype "bidirectional"))
    )
    (net (code "94") (name "B15_L24_P") (class "Default")
      (node (ref "JM2") (pin "39") (pinfunction "39_39") (pintype "bidirectional"))
    )
    (net (code "95") (name "B34_L1_N") (class "Default")
      (node (ref "JM1") (pin "37") (pinfunction "37_37") (pintype "bidirectional"))
    )
    (net (code "96") (name "B34_L1_P") (class "Default")
      (node (ref "JM1") (pin "35") (pinfunction "35_35") (pintype "bidirectional"))
    )
    (net (code "97") (name "B34_L2_N") (class "Default")
      (node (ref "JM1") (pin "33") (pinfunction "33_33") (pintype "bidirectional"))
    )
    (net (code "98") (name "B34_L2_P") (class "Default")
      (node (ref "JM1") (pin "31") (pinfunction "31_31") (pintype "bidirectional"))
    )
    (net (code "99") (name "B34_L3_N") (class "Default")
      (node (ref "JM1") (pin "42") (pinfunction "42_42") (pintype "bidirectional"))
    )
    (net (code "100") (name "B34_L3_P") (class "Default")
      (node (ref "JM1") (pin "40") (pinfunction "40_40") (pintype "bidirectional"))
    )
    (net (code "101") (name "B34_L4_N") (class "Default")
      (node (ref "JM1") (pin "41") (pinfunction "41_41") (pintype "bidirectional"))
    )
    (net (code "102") (name "B34_L4_P") (class "Default")
      (node (ref "JM1") (pin "39") (pinfunction "39_39") (pintype "bidirectional"))
    )
    (net (code "103") (name "B34_L5_N") (class "Default")
      (node (ref "JM1") (pin "45") (pinfunction "45_45") (pintype "bidirectional"))
    )
    (net (code "104") (name "B34_L5_P") (class "Default")
      (node (ref "JM1") (pin "43") (pinfunction "43_43") (pintype "bidirectional"))
    )
    (net (code "105") (name "B34_L6_N") (class "Default")
      (node (ref "JM1") (pin "34") (pinfunction "34_34") (pintype "bidirectional"))
    )
    (net (code "106") (name "B34_L6_P") (class "Default")
      (node (ref "JM1") (pin "32") (pinfunction "32_32") (pintype "bidirectional"))
    )
    (net (code "107") (name "B34_L7_N") (class "Default")
      (node (ref "JM1") (pin "38") (pinfunction "38_38") (pintype "bidirectional"))
    )
    (net (code "108") (name "B34_L7_P") (class "Default")
      (node (ref "JM1") (pin "36") (pinfunction "36_36") (pintype "bidirectional"))
    )
    (net (code "109") (name "B34_L8_N") (class "Default")
      (node (ref "JM1") (pin "52") (pinfunction "52_52") (pintype "bidirectional"))
    )
    (net (code "110") (name "B34_L8_P") (class "Default")
      (node (ref "JM1") (pin "50") (pinfunction "50_50") (pintype "bidirectional"))
    )
    (net (code "111") (name "B34_L9_N") (class "Default")
      (node (ref "JM1") (pin "46") (pinfunction "46_46") (pintype "bidirectional"))
    )
    (net (code "112") (name "B34_L9_P") (class "Default")
      (node (ref "JM1") (pin "44") (pinfunction "44_44") (pintype "bidirectional"))
    )
    (net (code "113") (name "B34_L10_N") (class "Default")
      (node (ref "JM1") (pin "51") (pinfunction "51_51") (pintype "bidirectional"))
    )
    (net (code "114") (name "B34_L10_P") (class "Default")
      (node (ref "JM1") (pin "49") (pinfunction "49_49") (pintype "bidirectional"))
    )
    (net (code "115") (name "B34_L11_N") (class "Default")
      (node (ref "JM1") (pin "53") (pinfunction "53_53") (pintype "bidirectional"))
    )
    (net (code "116") (name "B34_L11_P") (class "Default")
      (node (ref "JM1") (pin "55") (pinfunction "55_55") (pintype "bidirectional"))
    )
    (net (code "117") (name "B34_L12_N") (class "Default")
      (node (ref "JM1") (pin "57") (pinfunction "57_57") (pintype "bidirectional"))
    )
    (net (code "118") (name "B34_L12_P") (class "Default")
      (node (ref "JM1") (pin "59") (pinfunction "59_59") (pintype "bidirectional"))
    )
    (net (code "119") (name "B34_L13_N") (class "Default")
      (node (ref "JM1") (pin "56") (pinfunction "56_56") (pintype "bidirectional"))
    )
    (net (code "120") (name "B34_L13_P") (class "Default")
      (node (ref "JM1") (pin "54") (pinfunction "54_54") (pintype "bidirectional"))
    )
    (net (code "121") (name "B34_L14_N") (class "Default")
      (node (ref "JM1") (pin "60") (pinfunction "60_60") (pintype "bidirectional"))
    )
    (net (code "122") (name "B34_L14_P") (class "Default")
      (node (ref "JM1") (pin "58") (pinfunction "58_58") (pintype "bidirectional"))
    )
    (net (code "123") (name "B34_L15_N") (class "Default")
      (node (ref "JM1") (pin "62") (pinfunction "62_62") (pintype "bidirectional"))
    )
    (net (code "124") (name "B34_L15_P") (class "Default")
      (node (ref "JM1") (pin "64") (pinfunction "64_64") (pintype "bidirectional"))
    )
    (net (code "125") (name "B34_L16_N") (class "Default")
      (node (ref "JM1") (pin "68") (pinfunction "68_68") (pintype "bidirectional"))
    )
    (net (code "126") (name "B34_L16_P") (class "Default")
      (node (ref "JM1") (pin "70") (pinfunction "70_70") (pintype "bidirectional"))
    )
    (net (code "127") (name "B34_L17_N") (class "Default")
      (node (ref "JM1") (pin "63") (pinfunction "63_63") (pintype "bidirectional"))
    )
    (net (code "128") (name "B34_L17_P") (class "Default")
      (node (ref "JM1") (pin "65") (pinfunction "65_65") (pintype "bidirectional"))
    )
    (net (code "129") (name "B34_L18_N") (class "Default")
      (node (ref "JM1") (pin "74") (pinfunction "74_74") (pintype "bidirectional"))
    )
    (net (code "130") (name "B34_L18_P") (class "Default")
      (node (ref "JM1") (pin "72") (pinfunction "72_72") (pintype "bidirectional"))
    )
    (net (code "131") (name "B34_L19_N") (class "Default")
      (node (ref "JM1") (pin "71") (pinfunction "71_71") (pintype "bidirectional"))
    )
    (net (code "132") (name "B34_L19_P") (class "Default")
      (node (ref "JM1") (pin "73") (pinfunction "73_73") (pintype "bidirectional"))
    )
    (net (code "133") (name "B34_L20_N") (class "Default")
      (node (ref "JM1") (pin "76") (pinfunction "76_76") (pintype "bidirectional"))
    )
    (net (code "134") (name "B34_L20_P") (class "Default")
      (node (ref "JM1") (pin "78") (pinfunction "78_78") (pintype "bidirectional"))
    )
    (net (code "135") (name "B34_L21_N") (class "Default")
      (node (ref "JM1") (pin "69") (pinfunction "69_69") (pintype "bidirectional"))
    )
    (net (code "136") (name "B34_L21_P") (class "Default")
      (node (ref "JM1") (pin "67") (pinfunction "67_67") (pintype "bidirectional"))
    )
    (net (code "137") (name "B34_L22_N") (class "Default")
      (node (ref "JM1") (pin "75") (pinfunction "75_75") (pintype "bidirectional"))
    )
    (net (code "138") (name "B34_L22_P") (class "Default")
      (node (ref "JM1") (pin "77") (pinfunction "77_77") (pintype "bidirectional"))
    )
    (net (code "139") (name "B34_L23_N") (class "Default")
      (node (ref "JM1") (pin "79") (pinfunction "79_79") (pintype "bidirectional"))
    )
    (net (code "140") (name "B34_L23_P") (class "Default")
      (node (ref "JM1") (pin "81") (pinfunction "81_81") (pintype "bidirectional"))
    )
    (net (code "141") (name "B34_L24_N") (class "Default")
      (node (ref "JM1") (pin "80") (pinfunction "80_80") (pintype "bidirectional"))
    )
    (net (code "142") (name "B34_L24_P") (class "Default")
      (node (ref "JM1") (pin "82") (pinfunction "82_82") (pintype "bidirectional"))
    )
    (net (code "143") (name "BOOTMODE") (class "Default")
      (node (ref "JM2") (pin "100") (pinfunction "100_100") (pintype "bidirectional"))
    )
    (net (code "144") (name "DONE") (class "Default")
      (node (ref "D5") (pin "A") (pinfunction "A_A") (pintype "passive"))
      (node (ref "JM1") (pin "96") (pinfunction "96_96") (pintype "bidirectional"))
      (node (ref "R4") (pin "1") (pinfunction "1_1") (pintype "passive"))
    )
    (net (code "145") (name "EN_A") (class "Default")
      (node (ref "R18") (pin "1") (pinfunction "1_1") (pintype "passive"))
      (node (ref "U6") (pin "1") (pinfunction "EN_1") (pintype "input"))
    )
    (net (code "146") (name "EN_B") (class "Default")
      (node (ref "R21") (pin "1") (pinfunction "1_1") (pintype "passive"))
      (node (ref "U7") (pin "1") (pinfunction "EN_1") (pintype "input"))
    )
    (net (code "147") (name "GND") (class "Default")
      (node (ref "C1") (pin "2") (pinfunction "2_2") (pintype "passive"))
      (node (ref "C4") (pin "2") (pinfunction "2_2") (pintype "passive"))
      (node (ref "C56") (pin "2") (pinfunction "2_2") (pintype "passive"))
      (node (ref "C57") (pin "2") (pinfunction "2_2") (pintype "passive"))
      (node (ref "C58") (pin "2") (pinfunction "2_2") (pintype "passive"))
      (node (ref "C59") (pin "2") (pinfunction "2_2") (pintype "passive"))
      (node (ref "D5") (pin "C") (pinfunction "C_C") (pintype "passive"))
      (node (ref "JM1") (pin "100") (pinfunction "100_100") (pintype "bidirectional"))
      (node (ref "JM1") (pin "11") (pinfunction "11_11") (pintype "bidirectional"))
      (node (ref "JM1") (pin "12") (pinfunction "12_12") (pintype "bidirectional"))
      (node (ref "JM1") (pin "17") (pinfunction "17_17") (pintype "bidirectional"))
      (node (ref "JM1") (pin "18") (pinfunction "18_18") (pintype "bidirectional"))
      (node (ref "JM1") (pin "23") (pinfunction "23_23") (pintype "bidirectional"))
      (node (ref "JM1") (pin "24") (pinfunction "24_24") (pintype "bidirectional"))
      (node (ref "JM1") (pin "29") (pinfunction "29_29") (pintype "bidirectional"))
      (node (ref "JM1") (pin "30") (pinfunction "30_30") (pintype "bidirectional"))
      (node (ref "JM1") (pin "47") (pinfunction "47_47") (pintype "bidirectional"))
      (node (ref "JM1") (pin "48") (pinfunction "48_48") (pintype "bidirectional"))
      (node (ref "JM1") (pin "5") (pinfunction "5_5") (pintype "bidirectional"))
      (node (ref "JM1") (pin "6") (pinfunction "6_6") (pintype "bidirectional"))
      (node (ref "JM1") (pin "66") (pinfunction "66_66") (pintype "bidirectional"))
      (node (ref "JM1") (pin "84") (pinfunction "84_84") (pintype "bidirectional"))
      (node (ref "JM1") (pin "98") (pinfunction "98_98") (pintype "bidirectional"))
      (node (ref "JM1") (pin "F1") (pinfunction "F1_F1") (pintype "bidirectional"))
      (node (ref "JM1") (pin "F2") (pinfunction "F2_F2") (pintype "bidirectional"))
      (node (ref "JM2") (pin "17") (pinfunction "17_17") (pintype "bidirectional"))
      (node (ref "JM2") (pin "35") (pinfunction "35_35") (pintype "bidirectional"))
      (node (ref "JM2") (pin "36") (pinfunction "36_36") (pintype "bidirectional"))
      (node (ref "JM2") (pin "72") (pinfunction "72_72") (pintype "bidirectional"))
      (node (ref "JM2") (pin "83") (pinfunction "83_83") (pintype "bidirectional"))
      (node (ref "JM2") (pin "90") (pinfunction "90_90") (pintype "bidirectional"))
      (node (ref "JM2") (pin "F1") (pinfunction "F1_F1") (pintype "bidirectional"))
      (node (ref "JM2") (pin "F2") (pinfunction "F2_F2") (pintype "bidirectional"))
      (node (ref "JP1") (pin "3") (pinfunction "3_3") (pintype "passive"))
      (node (ref "JTAG") (pin "1") (pinfunction "1_1") (pintype "passive"))
      (node (ref "JTAG") (pin "11") (pinfunction "11_11") (pintype "passive"))
      (node (ref "JTAG") (pin "13") (pinfunction "13_13") (pintype "passive"))
      (node (ref "JTAG") (pin "3") (pinfunction "3_3") (pintype "passive"))
      (node (ref "JTAG") (pin "5") (pinfunction "5_5") (pintype "passive"))
      (node (ref "JTAG") (pin "7") (pinfunction "7_7") (pintype "passive"))
      (node (ref "JTAG") (pin "9") (pinfunction "9_9") (pintype "passive"))
      (node (ref "PCIE-NORTH") (pin "A1") (pinfunction "GND_A1") (pintype "passive"))
      (node (ref "PCIE-NORTH") (pin "A10") (pinfunction "GND_A10") (pintype "passive"))
      (node (ref "PCIE-NORTH") (pin "A12") (pinfunction "GND_A12") (pintype "passive"))
      (node (ref "PCIE-NORTH") (pin "A15") (pinfunction "GND_A15") (pintype "passive"))
      (node (ref "PCIE-NORTH") (pin "A18") (pinfunction "GND_A18") (pintype "passive"))
      (node (ref "PCIE-NORTH") (pin "A4") (pinfunction "GND_A4") (pintype "passive"))
      (node (ref "PCIE-NORTH") (pin "A7") (pinfunction "GND_A7") (pintype "passive"))
      (node (ref "PCIE-NORTH") (pin "B15") (pinfunction "GND_B15") (pintype "passive"))
      (node (ref "PCIE-NORTH") (pin "B18") (pinfunction "GND_B18") (pintype "passive"))
      (node (ref "PCIE-SOUTH") (pin "A1") (pinfunction "GND_A1") (pintype "passive"))
      (node (ref "PCIE-SOUTH") (pin "A10") (pinfunction "GND_A10") (pintype "passive"))
      (node (ref "PCIE-SOUTH") (pin "A12") (pinfunction "GND_A12") (pintype "passive"))
      (node (ref "PCIE-SOUTH") (pin "A15") (pinfunction "GND_A15") (pintype "passive"))
      (node (ref "PCIE-SOUTH") (pin "A18") (pinfunction "GND_A18") (pintype "passive"))
      (node (ref "PCIE-SOUTH") (pin "A4") (pinfunction "GND_A4") (pintype "passive"))
      (node (ref "PCIE-SOUTH") (pin "A7") (pinfunction "GND_A7") (pintype "passive"))
      (node (ref "PCIE-SOUTH") (pin "B15") (pinfunction "GND_B15") (pintype "passive"))
      (node (ref "PCIE-SOUTH") (pin "B18") (pinfunction "GND_B18") (pintype "passive"))
      (node (ref "R19") (pin "1") (pinfunction "1_1") (pintype "passive"))
      (node (ref "R22") (pin "1") (pinfunction "1_1") (pintype "passive"))
      (node (ref "R3") (pin "2") (pinfunction "2_2") (pintype "passive"))
      (node (ref "SATA0") (pin "1") (pinfunction "GND_1") (pintype "power_in"))
      (node (ref "SATA0") (pin "4") (pinfunction "GND_4") (pintype "power_in"))
      (node (ref "SATA0") (pin "7") (pinfunction "GND_7") (pintype "power_in"))
      (node (ref "SATA1") (pin "1") (pinfunction "GND_1") (pintype "power_in"))
      (node (ref "SATA1") (pin "4") (pinfunction "GND_4") (pintype "power_in"))
      (node (ref "SATA1") (pin "7") (pinfunction "GND_7") (pintype "power_in"))
      (node (ref "SATA2") (pin "1") (pinfunction "GND_1") (pintype "power_in"))
      (node (ref "SATA2") (pin "4") (pinfunction "GND_4") (pintype "power_in"))
      (node (ref "SATA2") (pin "7") (pinfunction "GND_7") (pintype "power_in"))
      (node (ref "SATA3") (pin "1") (pinfunction "GND_1") (pintype "power_in"))
      (node (ref "SATA3") (pin "4") (pinfunction "GND_4") (pintype "power_in"))
      (node (ref "SATA3") (pin "7") (pinfunction "GND_7") (pintype "power_in"))
      (node (ref "U1") (pin "3") (pinfunction "GND_3") (pintype "passive"))
      (node (ref "U2") (pin "1") (pinfunction "A0_1") (pintype "input"))
      (node (ref "U2") (pin "2") (pinfunction "A1_2") (pintype "input"))
      (node (ref "U2") (pin "3") (pinfunction "A2_3") (pintype "input"))
      (node (ref "U2") (pin "4") (pinfunction "GND_4") (pintype "passive"))
      (node (ref "U2") (pin "EP") (pinfunction "EP_EP") (pintype "passive"))
      (node (ref "U6") (pin "5") (pinfunction "GND_5") (pintype "passive"))
      (node (ref "U6") (pin "6") (pinfunction "GND_6") (pintype "passive"))
      (node (ref "U6") (pin "EP") (pinfunction "GND_EP") (pintype "passive"))
      (node (ref "U7") (pin "5") (pinfunction "GND_5") (pintype "passive"))
      (node (ref "U7") (pin "6") (pinfunction "GND_6") (pintype "passive"))
      (node (ref "U7") (pin "EP") (pinfunction "GND_EP") (pintype "passive"))
    )
    (net (code "148") (name "I2C_V") (class "Default")
      (node (ref "C4") (pin "1") (pinfunction "1_1") (pintype "passive"))
      (node (ref "PCIE-NORTH") (pin "B3") (pinfunction "V_I2C_B3") (pintype "passive"))
      (node (ref "R2") (pin "1") (pinfunction "1_1") (pintype "passive"))
      (node (ref "U2") (pin "8") (pinfunction "VCC_8") (pintype "power_in"))
    )
    (net (code "149") (name "MGT_CLK0_N") (class "Default")
      (node (ref "C3") (pin "2") (pinfunction "2_2") (pintype "passive"))
      (node (ref "JM1") (pin "4") (pinfunction "4_4") (pintype "bidirectional"))
    )
    (net (code "150") (name "MGT_CLK0_P") (class "Default")
      (node (ref "C2") (pin "2") (pinfunction "2_2") (pintype "passive"))
      (node (ref "JM1") (pin "2") (pinfunction "2_2") (pintype "bidirectional"))
    )
    (net (code "151") (name "MGT_RX0_N") (class "Default")
      (node (ref "JM1") (pin "21") (pinfunction "21_21") (pintype "bidirectional"))
      (node (ref "SATA3") (pin "5") (pinfunction "~{B}_5") (pintype "bidirectional"))
    )
    (net (code "152") (name "MGT_RX0_P") (class "Default")
      (node (ref "JM1") (pin "19") (pinfunction "19_19") (pintype "bidirectional"))
      (node (ref "SATA3") (pin "6") (pinfunction "B_6") (pintype "bidirectional"))
    )
    (net (code "153") (name "MGT_RX1_N") (class "Default")
      (node (ref "JM1") (pin "15") (pinfunction "15_15") (pintype "bidirectional"))
      (node (ref "SATA2") (pin "5") (pinfunction "~{B}_5") (pintype "bidirectional"))
    )
    (net (code "154") (name "MGT_RX1_P") (class "Default")
      (node (ref "JM1") (pin "13") (pinfunction "13_13") (pintype "bidirectional"))
      (node (ref "SATA2") (pin "6") (pinfunction "B_6") (pintype "bidirectional"))
    )
    (net (code "155") (name "MGT_RX2_N") (class "Default")
      (node (ref "JM1") (pin "9") (pinfunction "9_9") (pintype "bidirectional"))
      (node (ref "SATA1") (pin "5") (pinfunction "~{B}_5") (pintype "bidirectional"))
    )
    (net (code "156") (name "MGT_RX2_P") (class "Default")
      (node (ref "JM1") (pin "7") (pinfunction "7_7") (pintype "bidirectional"))
      (node (ref "SATA1") (pin "6") (pinfunction "B_6") (pintype "bidirectional"))
    )
    (net (code "157") (name "MGT_RX3_N") (class "Default")
      (node (ref "JM1") (pin "3") (pinfunction "3_3") (pintype "bidirectional"))
      (node (ref "SATA0") (pin "5") (pinfunction "~{B}_5") (pintype "bidirectional"))
    )
    (net (code "158") (name "MGT_RX3_P") (class "Default")
      (node (ref "JM1") (pin "1") (pinfunction "1_1") (pintype "bidirectional"))
      (node (ref "SATA0") (pin "6") (pinfunction "B_6") (pintype "bidirectional"))
    )
    (net (code "159") (name "MGT_TX0_N") (class "Default")
      (node (ref "JM1") (pin "28") (pinfunction "28_28") (pintype "bidirectional"))
      (node (ref "SATA3") (pin "3") (pinfunction "~{A}_3") (pintype "bidirectional"))
    )
    (net (code "160") (name "MGT_TX0_P") (class "Default")
      (node (ref "JM1") (pin "26") (pinfunction "26_26") (pintype "bidirectional"))
      (node (ref "SATA3") (pin "2") (pinfunction "A_2") (pintype "bidirectional"))
    )
    (net (code "161") (name "MGT_TX1_N") (class "Default")
      (node (ref "JM1") (pin "22") (pinfunction "22_22") (pintype "bidirectional"))
      (node (ref "SATA2") (pin "3") (pinfunction "~{A}_3") (pintype "bidirectional"))
    )
    (net (code "162") (name "MGT_TX1_P") (class "Default")
      (node (ref "JM1") (pin "20") (pinfunction "20_20") (pintype "bidirectional"))
      (node (ref "SATA2") (pin "2") (pinfunction "A_2") (pintype "bidirectional"))
    )
    (net (code "163") (name "MGT_TX2_N") (class "Default")
      (node (ref "JM1") (pin "16") (pinfunction "16_16") (pintype "bidirectional"))
      (node (ref "SATA1") (pin "3") (pinfunction "~{A}_3") (pintype "bidirectional"))
    )
    (net (code "164") (name "MGT_TX2_P") (class "Default")
      (node (ref "JM1") (pin "14") (pinfunction "14_14") (pintype "bidirectional"))
      (node (ref "SATA1") (pin "2") (pinfunction "A_2") (pintype "bidirectional"))
    )
    (net (code "165") (name "MGT_TX3_N") (class "Default")
      (node (ref "JM1") (pin "10") (pinfunction "10_10") (pintype "bidirectional"))
      (node (ref "SATA0") (pin "3") (pinfunction "~{A}_3") (pintype "bidirectional"))
    )
    (net (code "166") (name "MGT_TX3_P") (class "Default")
      (node (ref "JM1") (pin "8") (pinfunction "8_8") (pintype "bidirectional"))
      (node (ref "SATA0") (pin "2") (pinfunction "A_2") (pintype "bidirectional"))
    )
    (net (code "167") (name "M_1V8") (class "Default")
      (node (ref "JM2") (pin "18") (pinfunction "18_18") (pintype "bidirectional"))
    )
    (net (code "168") (name "N_5V") (class "Default")
      (node (ref "PCIE-NORTH") (pin "B12") (pinfunction "5V_B12") (pintype "passive"))
    )
    (net (code "169") (name "N_IO0") (class "Default")
      (node (ref "PCIE-NORTH") (pin "B4") (pinfunction "IO0_B4") (pintype "passive"))
    )
    (net (code "170") (name "N_IO1") (class "Default")
      (node (ref "PCIE-NORTH") (pin "B5") (pinfunction "IO1_B5") (pintype "passive"))
    )
    (net (code "171") (name "N_IO2") (class "Default")
      (node (ref "PCIE-NORTH") (pin "B6") (pinfunction "IO2_B6") (pintype "passive"))
    )
    (net (code "172") (name "N_IO3") (class "Default")
      (node (ref "PCIE-NORTH") (pin "B7") (pinfunction "IO3_B7") (pintype "passive"))
    )
    (net (code "173") (name "N_IO4") (class "Default")
      (node (ref "PCIE-NORTH") (pin "B8") (pinfunction "IO4_B8") (pintype "passive"))
    )
    (net (code "174") (name "N_IO5") (class "Default")
      (node (ref "PCIE-NORTH") (pin "B9") (pinfunction "IO5_B9") (pintype "passive"))
    )
    (net (code "175") (name "N_IO6") (class "Default")
      (node (ref "PCIE-NORTH") (pin "B10") (pinfunction "IO6_B10") (pintype "passive"))
    )
    (net (code "176") (name "N_IO7") (class "Default")
      (node (ref "PCIE-NORTH") (pin "B11") (pinfunction "IO7_B11") (pintype "passive"))
    )
    (net (code "177") (name "N_PCIE_V") (class "Default")
      (node (ref "PCIE-NORTH") (pin "B13") (pinfunction "VCC_B13") (pintype "passive"))
    )
    (net (code "178") (name "N_VCCIO") (class "Default")
      (node (ref "PCIE-NORTH") (pin "B14") (pinfunction "VCCIO_B14") (pintype "passive"))
    )
    (net (code "179") (name "Net-(D1-PadC)") (class "Default")
      (node (ref "D1") (pin "C") (pinfunction "C_C") (pintype "passive"))
      (node (ref "R6") (pin "2") (pinfunction "2_2") (pintype "passive"))
    )
    (net (code "180") (name "Net-(D2-PadC)") (class "Default")
      (node (ref "D2") (pin "C") (pinfunction "C_C") (pintype "passive"))
      (node (ref "R7") (pin "2") (pinfunction "2_2") (pintype "passive"))
    )
    (net (code "181") (name "Net-(D3-PadC)") (class "Default")
      (node (ref "D3") (pin "C") (pinfunction "C_C") (pintype "passive"))
      (node (ref "R8") (pin "2") (pinfunction "2_2") (pintype "passive"))
    )
    (net (code "182") (name "Net-(D4-PadC)") (class "Default")
      (node (ref "D4") (pin "C") (pinfunction "C_C") (pintype "passive"))
      (node (ref "R9") (pin "2") (pinfunction "2_2") (pintype "passive"))
    )
    (net (code "183") (name "Net-(U1-OUT+)") (class "Default")
      (node (ref "C2") (pin "1") (pinfunction "1_1") (pintype "passive"))
      (node (ref "R1") (pin "1") (pinfunction "1_1") (pintype "passive"))
      (node (ref "U1") (pin "4") (pinfunction "OUT+_4") (pintype "output"))
    )
    (net (code "184") (name "Net-(U1-OUT-)") (class "Default")
      (node (ref "C3") (pin "1") (pinfunction "1_1") (pintype "passive"))
      (node (ref "R1") (pin "2") (pinfunction "2_2") (pintype "passive"))
      (node (ref "U1") (pin "5") (pinfunction "OUT-_5") (pintype "output"))
    )
    (net (code "185") (name "Net-(U2-WP)") (class "Default")
      (node (ref "R2") (pin "2") (pinfunction "2_2") (pintype "passive"))
      (node (ref "R3") (pin "1") (pinfunction "1_1") (pintype "passive"))
      (node (ref "U2") (pin "7") (pinfunction "WP_7") (pintype "input"))
    )
    (net (code "186") (name "Net-(U6-FB)") (class "Default")
      (node (ref "R17") (pin "1") (pinfunction "1_1") (pintype "passive"))
      (node (ref "R19") (pin "2") (pinfunction "2_2") (pintype "passive"))
      (node (ref "U6") (pin "7") (pinfunction "FB_7") (pintype "output"))
    )
    (net (code "187") (name "Net-(U7-FB)") (class "Default")
      (node (ref "R20") (pin "1") (pinfunction "1_1") (pintype "passive"))
      (node (ref "R22") (pin "2") (pinfunction "2_2") (pintype "passive"))
      (node (ref "U7") (pin "7") (pinfunction "FB_7") (pintype "output"))
    )
    (net (code "188") (name "PROG_B") (class "Default")
      (node (ref "JM1") (pin "94") (pinfunction "94_94") (pintype "bidirectional"))
    )
    (net (code "189") (name "SCL") (class "Default")
      (node (ref "PCIE-NORTH") (pin "B2") (pinfunction "SCL_B2") (pintype "passive"))
      (node (ref "U2") (pin "6") (pinfunction "SCL_6") (pintype "input"))
    )
    (net (code "190") (name "SDA") (class "Default")
      (node (ref "PCIE-NORTH") (pin "B1") (pinfunction "SDA_B1") (pintype "passive"))
      (node (ref "U2") (pin "5") (pinfunction "SDA_5") (pintype "bidirectional"))
    )
    (net (code "191") (name "SPI-CLK") (class "Default")
      (node (ref "JM2") (pin "67") (pinfunction "67_67") (pintype "bidirectional"))
    )
    (net (code "192") (name "SPI-CS") (class "Default")
      (node (ref "JM2") (pin "69") (pinfunction "69_69") (pintype "bidirectional"))
    )
    (net (code "193") (name "SPI-DQ0") (class "Default")
      (node (ref "JM2") (pin "68") (pinfunction "68_68") (pintype "bidirectional"))
    )
    (net (code "194") (name "SPI-DQ1") (class "Default")
      (node (ref "JM2") (pin "71") (pinfunction "71_71") (pintype "bidirectional"))
    )
    (net (code "195") (name "SPI-DQ2") (class "Default")
      (node (ref "JM2") (pin "73") (pinfunction "73_73") (pintype "bidirectional"))
    )
    (net (code "196") (name "SPI-DQ3") (class "Default")
      (node (ref "JM2") (pin "70") (pinfunction "70_70") (pintype "bidirectional"))
    )
    (net (code "197") (name "S_5V") (class "Default")
      (node (ref "JP1") (pin "1") (pinfunction "1_1") (pintype "passive"))
      (node (ref "PCIE-SOUTH") (pin "B12") (pinfunction "5V_B12") (pintype "passive"))
    )
    (net (code "198") (name "S_PCIE_V") (class "Default")
      (node (ref "PCIE-SOUTH") (pin "B13") (pinfunction "VCC_B13") (pintype "passive"))
    )
    (net (code "199") (name "S_VCCIO") (class "Default")
      (node (ref "JM2") (pin "54") (pinfunction "54_54") (pintype "bidirectional"))
      (node (ref "PCIE-SOUTH") (pin "B14") (pinfunction "VCCIO_B14") (pintype "passive"))
    )
    (net (code "200") (name "TCK") (class "Default")
      (node (ref "JM1") (pin "90") (pinfunction "90_90") (pintype "bidirectional"))
      (node (ref "JTAG") (pin "6") (pinfunction "6_6") (pintype "passive"))
    )
    (net (code "201") (name "TDI") (class "Default")
      (node (ref "JM1") (pin "86") (pinfunction "86_86") (pintype "bidirectional"))
      (node (ref "JTAG") (pin "10") (pinfunction "10_10") (pintype "passive"))
    )
    (net (code "202") (name "TDO") (class "Default")
      (node (ref "JM1") (pin "88") (pinfunction "88_88") (pintype "bidirectional"))
      (node (ref "JTAG") (pin "8") (pinfunction "8_8") (pintype "passive"))
    )
    (net (code "203") (name "TMS") (class "Default")
      (node (ref "JM1") (pin "92") (pinfunction "92_92") (pintype "bidirectional"))
      (node (ref "JTAG") (pin "4") (pinfunction "4_4") (pintype "passive"))
    )
    (net (code "204") (name "VCCIO0") (class "Default")
      (node (ref "JM2") (pin "53") (pinfunction "53_53") (pintype "bidirectional"))
      (node (ref "JTAG") (pin "2") (pinfunction "2_2") (pintype "passive"))
    )
    (net (code "205") (name "VCCIO14") (class "Default")
      (node (ref "JM1") (pin "83") (pinfunction "83_83") (pintype "bidirectional"))
    )
    (net (code "206") (name "VCCIO34") (class "Default")
      (node (ref "JM1") (pin "61") (pinfunction "61_61") (pintype "bidirectional"))
    )
    (net (code "207") (name "VOUT_A") (class "Default")
      (node (ref "C57") (pin "1") (pinfunction "1_1") (pintype "passive"))
      (node (ref "FB11") (pin "1") (pinfunction "1_1") (pintype "passive"))
      (node (ref "R17") (pin "2") (pinfunction "2_2") (pintype "passive"))
      (node (ref "U6") (pin "8") (pinfunction "VOUT_8") (pintype "output"))
    )
    (net (code "208") (name "VOUT_B") (class "Default")
      (node (ref "C59") (pin "1") (pinfunction "1_1") (pintype "passive"))
      (node (ref "FB12") (pin "1") (pinfunction "1_1") (pintype "passive"))
      (node (ref "R20") (pin "2") (pinfunction "2_2") (pintype "passive"))
      (node (ref "U7") (pin "8") (pinfunction "VOUT_8") (pintype "output"))
    )
    (net (code "209") (name "VSUP") (class "Default")
      (node (ref "C56") (pin "1") (pinfunction "1_1") (pintype "passive"))
      (node (ref "C58") (pin "1") (pinfunction "1_1") (pintype "passive"))
      (node (ref "JP1") (pin "2") (pinfunction "2_2") (pintype "passive"))
      (node (ref "R18") (pin "2") (pinfunction "2_2") (pintype "passive"))
      (node (ref "R21") (pin "2") (pinfunction "2_2") (pintype "passive"))
      (node (ref "U6") (pin "3") (pinfunction "VIN_3") (pintype "power_in"))
      (node (ref "U6") (pin "4") (pinfunction "VIN_4") (pintype "power_in"))
      (node (ref "U7") (pin "3") (pinfunction "VIN_3") (pintype "power_in"))
      (node (ref "U7") (pin "4") (pinfunction "VIN_4") (pintype "power_in"))
    )
    (net (code "210") (name "V_CLK") (class "Default")
      (node (ref "C1") (pin "1") (pinfunction "1_1") (pintype "passive"))
      (node (ref "FB1") (pin "2") (pinfunction "2_2") (pintype "passive"))
      (node (ref "U1") (pin "6") (pinfunction "VCC_6") (pintype "power_in"))
    )
    (net (code "211") (name "unconnected-(GPIO-Pad1)") (class "Default")
      (node (ref "GPIO") (pin "1") (pinfunction "1_1") (pintype "passive"))
    )
    (net (code "212") (name "unconnected-(GPIO-Pad2)") (class "Default")
      (node (ref "GPIO") (pin "2") (pinfunction "2_2") (pintype "passive"))
    )
    (net (code "213") (name "unconnected-(GPIO-Pad3)") (class "Default")
      (node (ref "GPIO") (pin "3") (pinfunction "3_3") (pintype "passive"))
    )
    (net (code "214") (name "unconnected-(GPIO-Pad4)") (class "Default")
      (node (ref "GPIO") (pin "4") (pinfunction "4_4") (pintype "passive"))
    )
    (net (code "215") (name "unconnected-(GPIO-Pad5)") (class "Default")
      (node (ref "GPIO") (pin "5") (pinfunction "5_5") (pintype "passive"))
    )
    (net (code "216") (name "unconnected-(JTAG-Pad12)") (class "Default")
      (node (ref "JTAG") (pin "12") (pinfunction "12_12") (pintype "passive"))
    )
    (net (code "217") (name "unconnected-(JTAG-Pad14)") (class "Default")
      (node (ref "JTAG") (pin "14") (pinfunction "14_14") (pintype "passive"))
    )
    (net (code "218") (name "unconnected-(PCIE-NORTH-PWRGD-PadA11)") (class "Default")
      (node (ref "PCIE-NORTH") (pin "A11") (pinfunction "PWRGD_A11") (pintype "passive"))
    )
    (net (code "219") (name "unconnected-(PCIE-SOUTH-PWRGD-PadA11)") (class "Default")
      (node (ref "PCIE-SOUTH") (pin "A11") (pinfunction "PWRGD_A11") (pintype "passive"))
    )
    (net (code "220") (name "unconnected-(PCIE-SOUTH-SCL-PadB2)") (class "Default")
      (node (ref "PCIE-SOUTH") (pin "B2") (pinfunction "SCL_B2") (pintype "passive"))
    )
    (net (code "221") (name "unconnected-(PCIE-SOUTH-SDA-PadB1)") (class "Default")
      (node (ref "PCIE-SOUTH") (pin "B1") (pinfunction "SDA_B1") (pintype "passive"))
    )
    (net (code "222") (name "unconnected-(PCIE-SOUTH-V_I2C-PadB3)") (class "Default")
      (node (ref "PCIE-SOUTH") (pin "B3") (pinfunction "V_I2C_B3") (pintype "passive"))
    )
  )
)
